# W123X.net
KiCad netlist of a schematic drawn in EAGLE
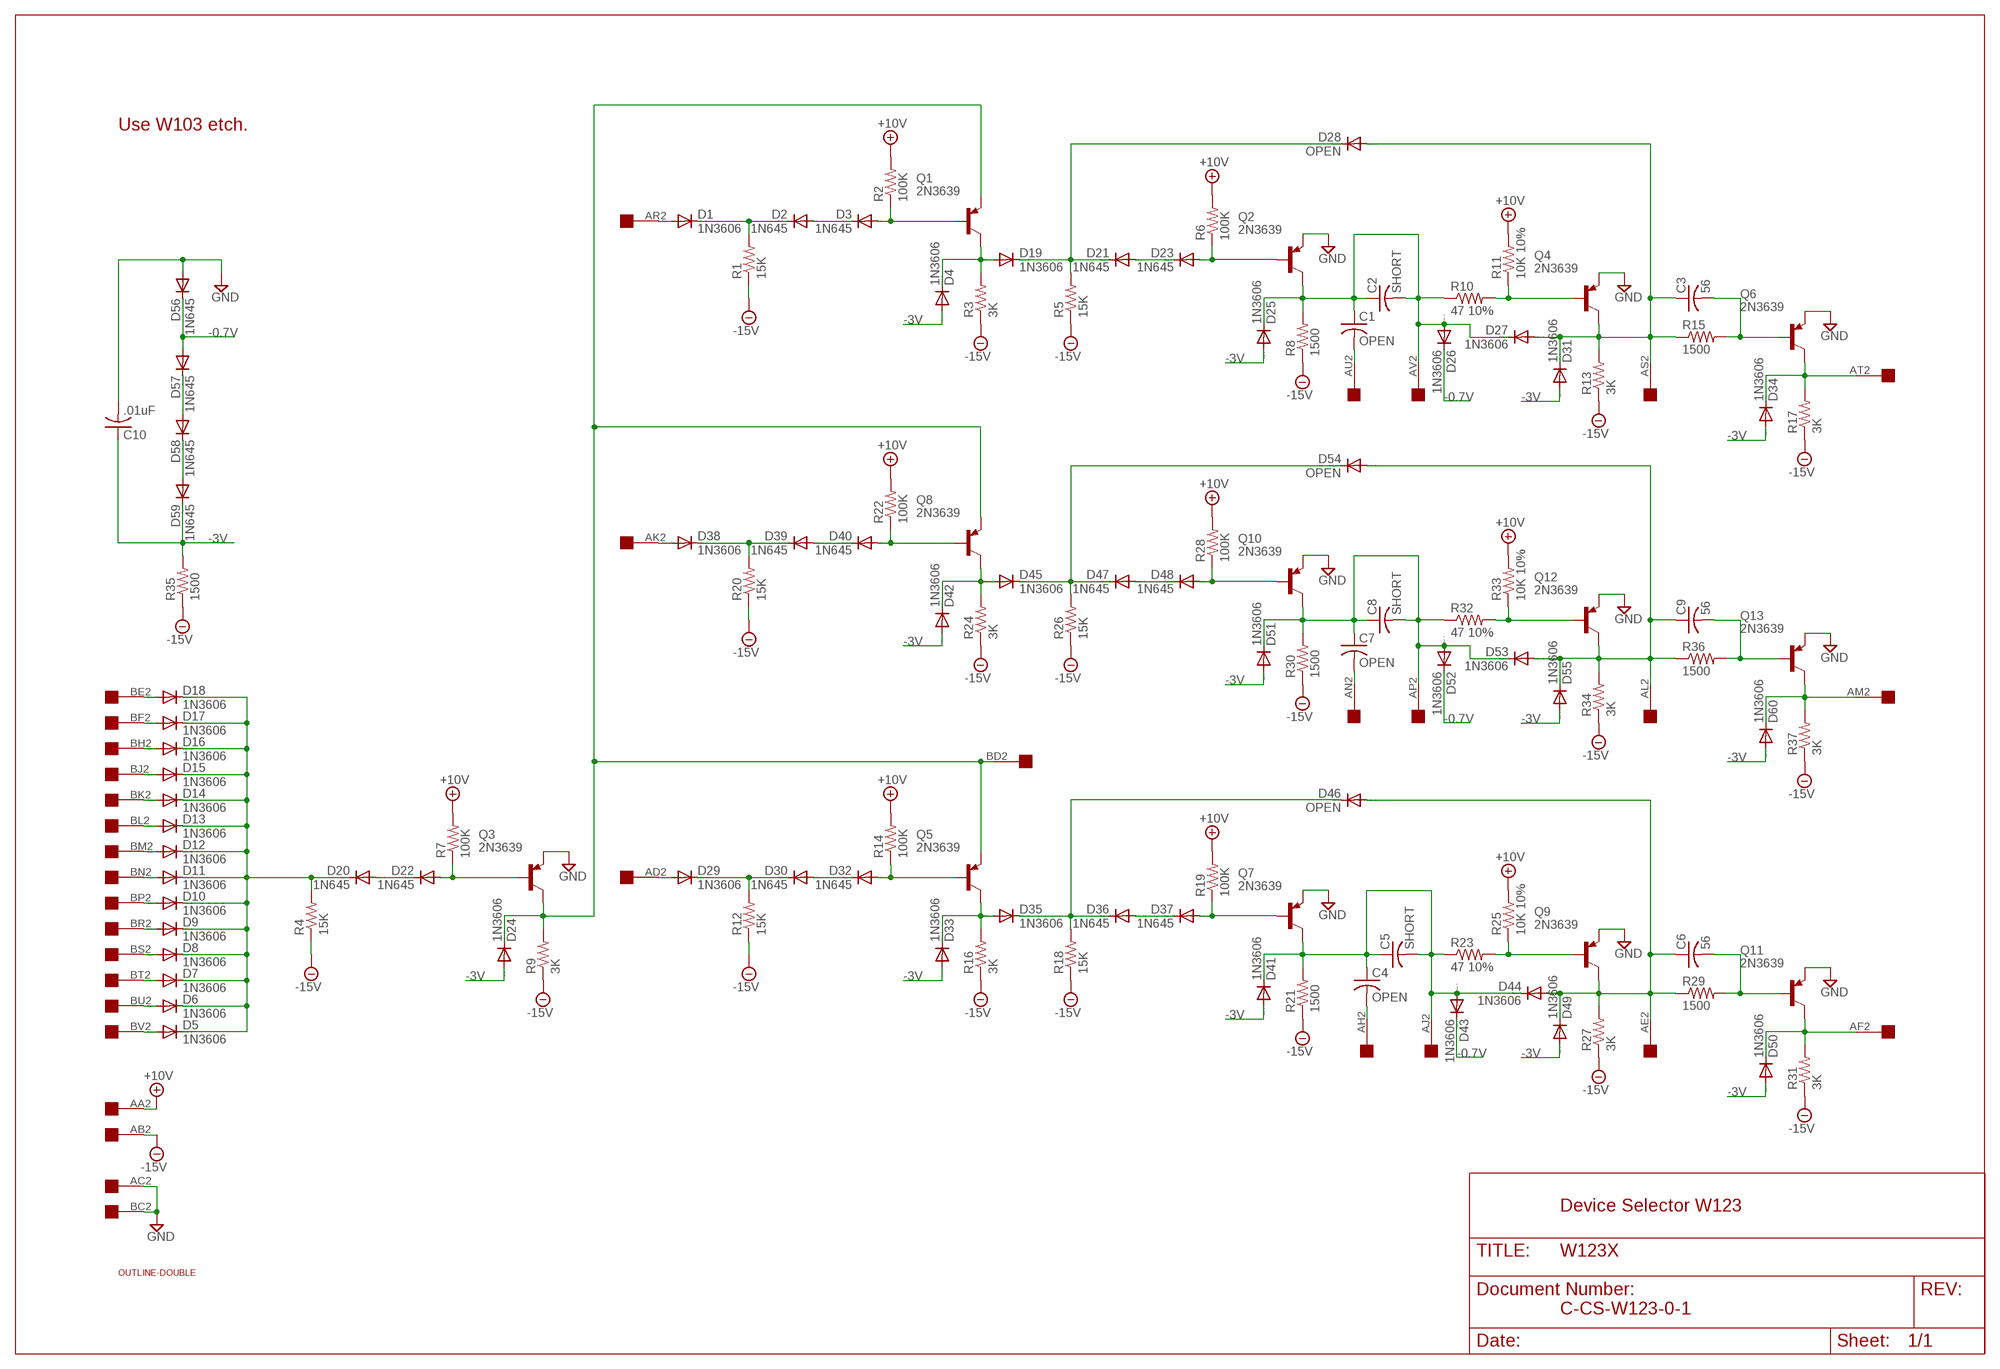
[diagram p0: schematic, sheet 1]

(export (version "E")
  (design (tool "Eeschema 10.0.6"))
  (components
    (comp (ref "C1")
      (value "OPEN")
      (footprint "eagle-import:C075-032X103")
      (libsource (lib "eagle-import") (part "C-US075-032X103"))
    )
    (comp (ref "C2")
      (value "SHORT")
      (footprint "eagle-import:C075-032X103")
      (libsource (lib "eagle-import") (part "C-US075-032X103"))
    )
    (comp (ref "C3")
      (value "56")
      (footprint "eagle-import:C075-032X103")
      (libsource (lib "eagle-import") (part "C-US075-032X103"))
    )
    (comp (ref "C4")
      (value "OPEN")
      (footprint "eagle-import:C075-032X103")
      (libsource (lib "eagle-import") (part "C-US075-032X103"))
    )
    (comp (ref "C5")
      (value "SHORT")
      (footprint "eagle-import:C075-032X103")
      (libsource (lib "eagle-import") (part "C-US075-032X103"))
    )
    (comp (ref "C6")
      (value "56")
      (footprint "eagle-import:C075-032X103")
      (libsource (lib "eagle-import") (part "C-US075-032X103"))
    )
    (comp (ref "C7")
      (value "OPEN")
      (footprint "eagle-import:C075-032X103")
      (libsource (lib "eagle-import") (part "C-US075-032X103"))
    )
    (comp (ref "C8")
      (value "SHORT")
      (footprint "eagle-import:C075-032X103")
      (libsource (lib "eagle-import") (part "C-US075-032X103"))
    )
    (comp (ref "C9")
      (value "56")
      (footprint "eagle-import:C075-032X103")
      (libsource (lib "eagle-import") (part "C-US075-032X103"))
    )
    (comp (ref "C10")
      (value ".01uF")
      (footprint "eagle-import:C075-032X103")
      (libsource (lib "eagle-import") (part "C-US075-032X103"))
    )
    (comp (ref "D1")
      (value "1N3606")
      (footprint "eagle-import:DO35-10")
      (libsource (lib "eagle-import") (part "1N4148DO35-10"))
    )
    (comp (ref "D2")
      (value "1N645")
      (footprint "eagle-import:DO35-10")
      (libsource (lib "eagle-import") (part "1N4148DO35-10"))
    )
    (comp (ref "D3")
      (value "1N645")
      (footprint "eagle-import:DO35-10")
      (libsource (lib "eagle-import") (part "1N4148DO35-10"))
    )
    (comp (ref "D4")
      (value "1N3606")
      (footprint "eagle-import:DO35-10")
      (libsource (lib "eagle-import") (part "1N4148DO35-10"))
    )
    (comp (ref "D5")
      (value "1N3606")
      (footprint "eagle-import:DO35-10")
      (libsource (lib "eagle-import") (part "1N4148DO35-10"))
    )
    (comp (ref "D6")
      (value "1N3606")
      (footprint "eagle-import:DO35-10")
      (libsource (lib "eagle-import") (part "1N4148DO35-10"))
    )
    (comp (ref "D7")
      (value "1N3606")
      (footprint "eagle-import:DO35-10")
      (libsource (lib "eagle-import") (part "1N4148DO35-10"))
    )
    (comp (ref "D8")
      (value "1N3606")
      (footprint "eagle-import:DO35-10")
      (libsource (lib "eagle-import") (part "1N4148DO35-10"))
    )
    (comp (ref "D9")
      (value "1N3606")
      (footprint "eagle-import:DO35-10")
      (libsource (lib "eagle-import") (part "1N4148DO35-10"))
    )
    (comp (ref "D10")
      (value "1N3606")
      (footprint "eagle-import:DO35-10")
      (libsource (lib "eagle-import") (part "1N4148DO35-10"))
    )
    (comp (ref "D11")
      (value "1N3606")
      (footprint "eagle-import:DO35-10")
      (libsource (lib "eagle-import") (part "1N4148DO35-10"))
    )
    (comp (ref "D12")
      (value "1N3606")
      (footprint "eagle-import:DO35-10")
      (libsource (lib "eagle-import") (part "1N4148DO35-10"))
    )
    (comp (ref "D13")
      (value "1N3606")
      (footprint "eagle-import:DO35-10")
      (libsource (lib "eagle-import") (part "1N4148DO35-10"))
    )
    (comp (ref "D14")
      (value "1N3606")
      (footprint "eagle-import:DO35-10")
      (libsource (lib "eagle-import") (part "1N4148DO35-10"))
    )
    (comp (ref "D15")
      (value "1N3606")
      (footprint "eagle-import:DO35-10")
      (libsource (lib "eagle-import") (part "1N4148DO35-10"))
    )
    (comp (ref "D16")
      (value "1N3606")
      (footprint "eagle-import:DO35-10")
      (libsource (lib "eagle-import") (part "1N4148DO35-10"))
    )
    (comp (ref "D17")
      (value "1N3606")
      (footprint "eagle-import:DO35-10")
      (libsource (lib "eagle-import") (part "1N4148DO35-10"))
    )
    (comp (ref "D18")
      (value "1N3606")
      (footprint "eagle-import:DO35-10")
      (libsource (lib "eagle-import") (part "1N4148DO35-10"))
    )
    (comp (ref "D19")
      (value "1N3606")
      (footprint "eagle-import:DO35-10")
      (libsource (lib "eagle-import") (part "1N4148DO35-10"))
    )
    (comp (ref "D20")
      (value "1N645")
      (footprint "eagle-import:DO35-10")
      (libsource (lib "eagle-import") (part "1N4148DO35-10"))
    )
    (comp (ref "D21")
      (value "1N645")
      (footprint "eagle-import:DO35-10")
      (libsource (lib "eagle-import") (part "1N4148DO35-10"))
    )
    (comp (ref "D22")
      (value "1N645")
      (footprint "eagle-import:DO35-10")
      (libsource (lib "eagle-import") (part "1N4148DO35-10"))
    )
    (comp (ref "D23")
      (value "1N645")
      (footprint "eagle-import:DO35-10")
      (libsource (lib "eagle-import") (part "1N4148DO35-10"))
    )
    (comp (ref "D24")
      (value "1N3606")
      (footprint "eagle-import:DO35-10")
      (libsource (lib "eagle-import") (part "1N4148DO35-10"))
    )
    (comp (ref "D25")
      (value "1N3606")
      (footprint "eagle-import:DO35-10")
      (libsource (lib "eagle-import") (part "1N4148DO35-10"))
    )
    (comp (ref "D26")
      (value "1N3606")
      (footprint "eagle-import:DO35-10")
      (libsource (lib "eagle-import") (part "1N4148DO35-10"))
    )
    (comp (ref "D27")
      (value "1N3606")
      (footprint "eagle-import:DO35-10")
      (libsource (lib "eagle-import") (part "1N4148DO35-10"))
    )
    (comp (ref "D28")
      (value "OPEN")
      (footprint "eagle-import:DO35-10")
      (libsource (lib "eagle-import") (part "1N4148DO35-10"))
    )
    (comp (ref "D29")
      (value "1N3606")
      (footprint "eagle-import:DO35-10")
      (libsource (lib "eagle-import") (part "1N4148DO35-10"))
    )
    (comp (ref "D30")
      (value "1N645")
      (footprint "eagle-import:DO35-10")
      (libsource (lib "eagle-import") (part "1N4148DO35-10"))
    )
    (comp (ref "D31")
      (value "1N3606")
      (footprint "eagle-import:DO35-10")
      (libsource (lib "eagle-import") (part "1N4148DO35-10"))
    )
    (comp (ref "D32")
      (value "1N645")
      (footprint "eagle-import:DO35-10")
      (libsource (lib "eagle-import") (part "1N4148DO35-10"))
    )
    (comp (ref "D33")
      (value "1N3606")
      (footprint "eagle-import:DO35-10")
      (libsource (lib "eagle-import") (part "1N4148DO35-10"))
    )
    (comp (ref "D34")
      (value "1N3606")
      (footprint "eagle-import:DO35-10")
      (libsource (lib "eagle-import") (part "1N4148DO35-10"))
    )
    (comp (ref "D35")
      (value "1N3606")
      (footprint "eagle-import:DO35-10")
      (libsource (lib "eagle-import") (part "1N4148DO35-10"))
    )
    (comp (ref "D36")
      (value "1N645")
      (footprint "eagle-import:DO35-10")
      (libsource (lib "eagle-import") (part "1N4148DO35-10"))
    )
    (comp (ref "D37")
      (value "1N645")
      (footprint "eagle-import:DO35-10")
      (libsource (lib "eagle-import") (part "1N4148DO35-10"))
    )
    (comp (ref "D38")
      (value "1N3606")
      (footprint "eagle-import:DO35-10")
      (libsource (lib "eagle-import") (part "1N4148DO35-10"))
    )
    (comp (ref "D39")
      (value "1N645")
      (footprint "eagle-import:DO35-10")
      (libsource (lib "eagle-import") (part "1N4148DO35-10"))
    )
    (comp (ref "D40")
      (value "1N645")
      (footprint "eagle-import:DO35-10")
      (libsource (lib "eagle-import") (part "1N4148DO35-10"))
    )
    (comp (ref "D41")
      (value "1N3606")
      (footprint "eagle-import:DO35-10")
      (libsource (lib "eagle-import") (part "1N4148DO35-10"))
    )
    (comp (ref "D42")
      (value "1N3606")
      (footprint "eagle-import:DO35-10")
      (libsource (lib "eagle-import") (part "1N4148DO35-10"))
    )
    (comp (ref "D43")
      (value "1N3606")
      (footprint "eagle-import:DO35-10")
      (libsource (lib "eagle-import") (part "1N4148DO35-10"))
    )
    (comp (ref "D44")
      (value "1N3606")
      (footprint "eagle-import:DO35-10")
      (libsource (lib "eagle-import") (part "1N4148DO35-10"))
    )
    (comp (ref "D45")
      (value "1N3606")
      (footprint "eagle-import:DO35-10")
      (libsource (lib "eagle-import") (part "1N4148DO35-10"))
    )
    (comp (ref "D46")
      (value "OPEN")
      (footprint "eagle-import:DO35-10")
      (libsource (lib "eagle-import") (part "1N4148DO35-10"))
    )
    (comp (ref "D47")
      (value "1N645")
      (footprint "eagle-import:DO35-10")
      (libsource (lib "eagle-import") (part "1N4148DO35-10"))
    )
    (comp (ref "D48")
      (value "1N645")
      (footprint "eagle-import:DO35-10")
      (libsource (lib "eagle-import") (part "1N4148DO35-10"))
    )
    (comp (ref "D49")
      (value "1N3606")
      (footprint "eagle-import:DO35-10")
      (libsource (lib "eagle-import") (part "1N4148DO35-10"))
    )
    (comp (ref "D50")
      (value "1N3606")
      (footprint "eagle-import:DO35-10")
      (libsource (lib "eagle-import") (part "1N4148DO35-10"))
    )
    (comp (ref "D51")
      (value "1N3606")
      (footprint "eagle-import:DO35-10")
      (libsource (lib "eagle-import") (part "1N4148DO35-10"))
    )
    (comp (ref "D52")
      (value "1N3606")
      (footprint "eagle-import:DO35-10")
      (libsource (lib "eagle-import") (part "1N4148DO35-10"))
    )
    (comp (ref "D53")
      (value "1N3606")
      (footprint "eagle-import:DO35-10")
      (libsource (lib "eagle-import") (part "1N4148DO35-10"))
    )
    (comp (ref "D54")
      (value "OPEN")
      (footprint "eagle-import:DO35-10")
      (libsource (lib "eagle-import") (part "1N4148DO35-10"))
    )
    (comp (ref "D55")
      (value "1N3606")
      (footprint "eagle-import:DO35-10")
      (libsource (lib "eagle-import") (part "1N4148DO35-10"))
    )
    (comp (ref "D56")
      (value "1N645")
      (footprint "eagle-import:DO35-10")
      (libsource (lib "eagle-import") (part "1N4148DO35-10"))
    )
    (comp (ref "D57")
      (value "1N645")
      (footprint "eagle-import:DO35-10")
      (libsource (lib "eagle-import") (part "1N4148DO35-10"))
    )
    (comp (ref "D58")
      (value "1N645")
      (footprint "eagle-import:DO35-10")
      (libsource (lib "eagle-import") (part "1N4148DO35-10"))
    )
    (comp (ref "D59")
      (value "1N645")
      (footprint "eagle-import:DO35-10")
      (libsource (lib "eagle-import") (part "1N4148DO35-10"))
    )
    (comp (ref "D60")
      (value "1N3606")
      (footprint "eagle-import:DO35-10")
      (libsource (lib "eagle-import") (part "1N4148DO35-10"))
    )
    (comp (ref "Q1")
      (value "2N3639")
      (footprint "eagle-import:TO39")
      (libsource (lib "eagle-import") (part "2N2904"))
    )
    (comp (ref "Q2")
      (value "2N3639")
      (footprint "eagle-import:TO39")
      (libsource (lib "eagle-import") (part "2N2904"))
    )
    (comp (ref "Q3")
      (value "2N3639")
      (footprint "eagle-import:TO39")
      (libsource (lib "eagle-import") (part "2N2904"))
    )
    (comp (ref "Q4")
      (value "2N3639")
      (footprint "eagle-import:TO39")
      (libsource (lib "eagle-import") (part "2N2904"))
    )
    (comp (ref "Q5")
      (value "2N3639")
      (footprint "eagle-import:TO39")
      (libsource (lib "eagle-import") (part "2N2904"))
    )
    (comp (ref "Q6")
      (value "2N3639")
      (footprint "eagle-import:TO39")
      (libsource (lib "eagle-import") (part "2N2904"))
    )
    (comp (ref "Q7")
      (value "2N3639")
      (footprint "eagle-import:TO39")
      (libsource (lib "eagle-import") (part "2N2904"))
    )
    (comp (ref "Q8")
      (value "2N3639")
      (footprint "eagle-import:TO39")
      (libsource (lib "eagle-import") (part "2N2904"))
    )
    (comp (ref "Q9")
      (value "2N3639")
      (footprint "eagle-import:TO39")
      (libsource (lib "eagle-import") (part "2N2904"))
    )
    (comp (ref "Q10")
      (value "2N3639")
      (footprint "eagle-import:TO39")
      (libsource (lib "eagle-import") (part "2N2904"))
    )
    (comp (ref "Q11")
      (value "2N3639")
      (footprint "eagle-import:TO39")
      (libsource (lib "eagle-import") (part "2N2904"))
    )
    (comp (ref "Q12")
      (value "2N3639")
      (footprint "eagle-import:TO39")
      (libsource (lib "eagle-import") (part "2N2904"))
    )
    (comp (ref "Q13")
      (value "2N3639")
      (footprint "eagle-import:TO39")
      (libsource (lib "eagle-import") (part "2N2904"))
    )
    (comp (ref "R1")
      (value "15K")
      (footprint "eagle-import:0207_10")
      (libsource (lib "eagle-import") (part "R-US_0207/10"))
    )
    (comp (ref "R2")
      (value "100K")
      (footprint "eagle-import:0207_10")
      (libsource (lib "eagle-import") (part "R-US_0207/10"))
    )
    (comp (ref "R3")
      (value "3K")
      (footprint "eagle-import:0207_10")
      (libsource (lib "eagle-import") (part "R-US_0207/10"))
    )
    (comp (ref "R4")
      (value "15K")
      (footprint "eagle-import:0207_10")
      (libsource (lib "eagle-import") (part "R-US_0207/10"))
    )
    (comp (ref "R5")
      (value "15K")
      (footprint "eagle-import:0207_10")
      (libsource (lib "eagle-import") (part "R-US_0207/10"))
    )
    (comp (ref "R6")
      (value "100K")
      (footprint "eagle-import:0207_10")
      (libsource (lib "eagle-import") (part "R-US_0207/10"))
    )
    (comp (ref "R7")
      (value "100K")
      (footprint "eagle-import:0207_10")
      (libsource (lib "eagle-import") (part "R-US_0207/10"))
    )
    (comp (ref "R8")
      (value "1500")
      (footprint "eagle-import:0207_10")
      (libsource (lib "eagle-import") (part "R-US_0207/10"))
    )
    (comp (ref "R9")
      (value "3K")
      (footprint "eagle-import:0207_10")
      (libsource (lib "eagle-import") (part "R-US_0207/10"))
    )
    (comp (ref "R10")
      (value "47 10%")
      (footprint "eagle-import:0207_10")
      (libsource (lib "eagle-import") (part "R-US_0207/10"))
    )
    (comp (ref "R11")
      (value "10K 10%")
      (footprint "eagle-import:0207_10")
      (libsource (lib "eagle-import") (part "R-US_0207/10"))
    )
    (comp (ref "R12")
      (value "15K")
      (footprint "eagle-import:0207_10")
      (libsource (lib "eagle-import") (part "R-US_0207/10"))
    )
    (comp (ref "R13")
      (value "3K")
      (footprint "eagle-import:0207_10")
      (libsource (lib "eagle-import") (part "R-US_0207/10"))
    )
    (comp (ref "R14")
      (value "100K")
      (footprint "eagle-import:0207_10")
      (libsource (lib "eagle-import") (part "R-US_0207/10"))
    )
    (comp (ref "R15")
      (value "1500")
      (footprint "eagle-import:0207_10")
      (libsource (lib "eagle-import") (part "R-US_0207/10"))
    )
    (comp (ref "R16")
      (value "3K")
      (footprint "eagle-import:0207_10")
      (libsource (lib "eagle-import") (part "R-US_0207/10"))
    )
    (comp (ref "R17")
      (value "3K")
      (footprint "eagle-import:0207_10")
      (libsource (lib "eagle-import") (part "R-US_0207/10"))
    )
    (comp (ref "R18")
      (value "15K")
      (footprint "eagle-import:0207_10")
      (libsource (lib "eagle-import") (part "R-US_0207/10"))
    )
    (comp (ref "R19")
      (value "100K")
      (footprint "eagle-import:0207_10")
      (libsource (lib "eagle-import") (part "R-US_0207/10"))
    )
    (comp (ref "R20")
      (value "15K")
      (footprint "eagle-import:0207_10")
      (libsource (lib "eagle-import") (part "R-US_0207/10"))
    )
    (comp (ref "R21")
      (value "1500")
      (footprint "eagle-import:0207_10")
      (libsource (lib "eagle-import") (part "R-US_0207/10"))
    )
    (comp (ref "R22")
      (value "100K")
      (footprint "eagle-import:0207_10")
      (libsource (lib "eagle-import") (part "R-US_0207/10"))
    )
    (comp (ref "R23")
      (value "47 10%")
      (footprint "eagle-import:0207_10")
      (libsource (lib "eagle-import") (part "R-US_0207/10"))
    )
    (comp (ref "R24")
      (value "3K")
      (footprint "eagle-import:0207_10")
      (libsource (lib "eagle-import") (part "R-US_0207/10"))
    )
    (comp (ref "R25")
      (value "10K 10%")
      (footprint "eagle-import:0207_10")
      (libsource (lib "eagle-import") (part "R-US_0207/10"))
    )
    (comp (ref "R26")
      (value "15K")
      (footprint "eagle-import:0207_10")
      (libsource (lib "eagle-import") (part "R-US_0207/10"))
    )
    (comp (ref "R27")
      (value "3K")
      (footprint "eagle-import:0207_10")
      (libsource (lib "eagle-import") (part "R-US_0207/10"))
    )
    (comp (ref "R28")
      (value "100K")
      (footprint "eagle-import:0207_10")
      (libsource (lib "eagle-import") (part "R-US_0207/10"))
    )
    (comp (ref "R29")
      (value "1500")
      (footprint "eagle-import:0207_10")
      (libsource (lib "eagle-import") (part "R-US_0207/10"))
    )
    (comp (ref "R30")
      (value "1500")
      (footprint "eagle-import:0207_10")
      (libsource (lib "eagle-import") (part "R-US_0207/10"))
    )
    (comp (ref "R31")
      (value "3K")
      (footprint "eagle-import:0207_10")
      (libsource (lib "eagle-import") (part "R-US_0207/10"))
    )
    (comp (ref "R32")
      (value "47 10%")
      (footprint "eagle-import:0207_10")
      (libsource (lib "eagle-import") (part "R-US_0207/10"))
    )
    (comp (ref "R33")
      (value "10K 10%")
      (footprint "eagle-import:0207_10")
      (libsource (lib "eagle-import") (part "R-US_0207/10"))
    )
    (comp (ref "R34")
      (value "3K")
      (footprint "eagle-import:0207_10")
      (libsource (lib "eagle-import") (part "R-US_0207/10"))
    )
    (comp (ref "R35")
      (value "1500")
      (footprint "eagle-import:0207_10")
      (libsource (lib "eagle-import") (part "R-US_0207/10"))
    )
    (comp (ref "R36")
      (value "1500")
      (footprint "eagle-import:0207_10")
      (libsource (lib "eagle-import") (part "R-US_0207/10"))
    )
    (comp (ref "R37")
      (value "3K")
      (footprint "eagle-import:0207_10")
      (libsource (lib "eagle-import") (part "R-US_0207/10"))
    )
    (comp (ref "U$1")
      (value "OUTLINE-DOUBLE")
      (footprint "eagle-import:DOUBLE")
      (libsource (lib "eagle-import") (part "OUTLINE-DOUBLE"))
    )
    (comp (ref "U$2")
      (value "DOUBLE")
      (footprint "eagle-import:EDGE-CON4")
      (libsource (lib "eagle-import") (part "DOUBLE"))
    )
  )
  (nets
    (net (code "1") (name "+10V") (class "Default")
      (node (ref "R11") (pin "2") (pinfunction "2_2") (pintype "passive"))
      (node (ref "R14") (pin "2") (pinfunction "2_2") (pintype "passive"))
      (node (ref "R19") (pin "2") (pinfunction "2_2") (pintype "passive"))
      (node (ref "R2") (pin "2") (pinfunction "2_2") (pintype "passive"))
      (node (ref "R22") (pin "2") (pinfunction "2_2") (pintype "passive"))
      (node (ref "R25") (pin "2") (pinfunction "2_2") (pintype "passive"))
      (node (ref "R28") (pin "2") (pinfunction "2_2") (pintype "passive"))
      (node (ref "R33") (pin "2") (pinfunction "2_2") (pintype "passive"))
      (node (ref "R6") (pin "2") (pinfunction "2_2") (pintype "passive"))
      (node (ref "R7") (pin "2") (pinfunction "2_2") (pintype "passive"))
      (node (ref "U$2") (pin "AA2") (pinfunction "1_AA2") (pintype "bidirectional"))
    )
    (net (code "2") (name "-15V") (class "Default")
      (node (ref "R1") (pin "1") (pinfunction "1_1") (pintype "passive"))
      (node (ref "R12") (pin "1") (pinfunction "1_1") (pintype "passive"))
      (node (ref "R13") (pin "1") (pinfunction "1_1") (pintype "passive"))
      (node (ref "R16") (pin "1") (pinfunction "1_1") (pintype "passive"))
      (node (ref "R17") (pin "1") (pinfunction "1_1") (pintype "passive"))
      (node (ref "R18") (pin "1") (pinfunction "1_1") (pintype "passive"))
      (node (ref "R20") (pin "1") (pinfunction "1_1") (pintype "passive"))
      (node (ref "R21") (pin "1") (pinfunction "1_1") (pintype "passive"))
      (node (ref "R24") (pin "1") (pinfunction "1_1") (pintype "passive"))
      (node (ref "R26") (pin "1") (pinfunction "1_1") (pintype "passive"))
      (node (ref "R27") (pin "1") (pinfunction "1_1") (pintype "passive"))
      (node (ref "R3") (pin "1") (pinfunction "1_1") (pintype "passive"))
      (node (ref "R30") (pin "1") (pinfunction "1_1") (pintype "passive"))
      (node (ref "R31") (pin "1") (pinfunction "1_1") (pintype "passive"))
      (node (ref "R34") (pin "1") (pinfunction "1_1") (pintype "passive"))
      (node (ref "R35") (pin "1") (pinfunction "1_1") (pintype "passive"))
      (node (ref "R37") (pin "1") (pinfunction "1_1") (pintype "passive"))
      (node (ref "R4") (pin "1") (pinfunction "1_1") (pintype "passive"))
      (node (ref "R5") (pin "1") (pinfunction "1_1") (pintype "passive"))
      (node (ref "R8") (pin "1") (pinfunction "1_1") (pintype "passive"))
      (node (ref "R9") (pin "1") (pinfunction "1_1") (pintype "passive"))
      (node (ref "U$2") (pin "AB2") (pinfunction "1_AB2") (pintype "bidirectional"))
    )
    (net (code "3") (name "/-0.7V") (class "Default")
      (node (ref "D26") (pin "C") (pinfunction "C_C") (pintype "passive"))
      (node (ref "D43") (pin "C") (pinfunction "C_C") (pintype "passive"))
      (node (ref "D52") (pin "C") (pinfunction "C_C") (pintype "passive"))
      (node (ref "D56") (pin "C") (pinfunction "C_C") (pintype "passive"))
      (node (ref "D57") (pin "A") (pinfunction "A_A") (pintype "passive"))
    )
    (net (code "4") (name "/-3V") (class "Default")
      (node (ref "C10") (pin "1") (pinfunction "1_1") (pintype "passive"))
      (node (ref "D24") (pin "A") (pinfunction "A_A") (pintype "passive"))
      (node (ref "D25") (pin "A") (pinfunction "A_A") (pintype "passive"))
      (node (ref "D31") (pin "A") (pinfunction "A_A") (pintype "passive"))
      (node (ref "D33") (pin "A") (pinfunction "A_A") (pintype "passive"))
      (node (ref "D34") (pin "A") (pinfunction "A_A") (pintype "passive"))
      (node (ref "D4") (pin "A") (pinfunction "A_A") (pintype "passive"))
      (node (ref "D41") (pin "A") (pinfunction "A_A") (pintype "passive"))
      (node (ref "D42") (pin "A") (pinfunction "A_A") (pintype "passive"))
      (node (ref "D49") (pin "A") (pinfunction "A_A") (pintype "passive"))
      (node (ref "D50") (pin "A") (pinfunction "A_A") (pintype "passive"))
      (node (ref "D51") (pin "A") (pinfunction "A_A") (pintype "passive"))
      (node (ref "D55") (pin "A") (pinfunction "A_A") (pintype "passive"))
      (node (ref "D59") (pin "C") (pinfunction "C_C") (pintype "passive"))
      (node (ref "D60") (pin "A") (pinfunction "A_A") (pintype "passive"))
      (node (ref "R35") (pin "2") (pinfunction "2_2") (pintype "passive"))
    )
    (net (code "5") (name "GND") (class "Default")
      (node (ref "C10") (pin "2") (pinfunction "2_2") (pintype "passive"))
      (node (ref "D56") (pin "A") (pinfunction "A_A") (pintype "passive"))
      (node (ref "Q10") (pin "1") (pinfunction "E_1") (pintype "passive"))
      (node (ref "Q11") (pin "1") (pinfunction "E_1") (pintype "passive"))
      (node (ref "Q12") (pin "1") (pinfunction "E_1") (pintype "passive"))
      (node (ref "Q13") (pin "1") (pinfunction "E_1") (pintype "passive"))
      (node (ref "Q2") (pin "1") (pinfunction "E_1") (pintype "passive"))
      (node (ref "Q3") (pin "1") (pinfunction "E_1") (pintype "passive"))
      (node (ref "Q4") (pin "1") (pinfunction "E_1") (pintype "passive"))
      (node (ref "Q6") (pin "1") (pinfunction "E_1") (pintype "passive"))
      (node (ref "Q7") (pin "1") (pinfunction "E_1") (pintype "passive"))
      (node (ref "Q9") (pin "1") (pinfunction "E_1") (pintype "passive"))
      (node (ref "U$2") (pin "AC2") (pinfunction "1_AC2") (pintype "bidirectional"))
      (node (ref "U$2") (pin "BC2") (pinfunction "1_BC2") (pintype "bidirectional"))
    )
    (net (code "6") (name "Net-(D1-PadC)") (class "Default")
      (node (ref "D1") (pin "C") (pinfunction "C_C") (pintype "passive"))
      (node (ref "D2") (pin "C") (pinfunction "C_C") (pintype "passive"))
      (node (ref "R1") (pin "2") (pinfunction "2_2") (pintype "passive"))
    )
    (net (code "7") (name "Net-(D2-PadA)") (class "Default")
      (node (ref "D2") (pin "A") (pinfunction "A_A") (pintype "passive"))
      (node (ref "D3") (pin "C") (pinfunction "C_C") (pintype "passive"))
    )
    (net (code "8") (name "Net-(D10-PadC)") (class "Default")
      (node (ref "D10") (pin "C") (pinfunction "C_C") (pintype "passive"))
      (node (ref "D11") (pin "C") (pinfunction "C_C") (pintype "passive"))
      (node (ref "D12") (pin "C") (pinfunction "C_C") (pintype "passive"))
      (node (ref "D13") (pin "C") (pinfunction "C_C") (pintype "passive"))
      (node (ref "D14") (pin "C") (pinfunction "C_C") (pintype "passive"))
      (node (ref "D15") (pin "C") (pinfunction "C_C") (pintype "passive"))
      (node (ref "D16") (pin "C") (pinfunction "C_C") (pintype "passive"))
      (node (ref "D17") (pin "C") (pinfunction "C_C") (pintype "passive"))
      (node (ref "D18") (pin "C") (pinfunction "C_C") (pintype "passive"))
      (node (ref "D20") (pin "C") (pinfunction "C_C") (pintype "passive"))
      (node (ref "D5") (pin "C") (pinfunction "C_C") (pintype "passive"))
      (node (ref "D6") (pin "C") (pinfunction "C_C") (pintype "passive"))
      (node (ref "D7") (pin "C") (pinfunction "C_C") (pintype "passive"))
      (node (ref "D8") (pin "C") (pinfunction "C_C") (pintype "passive"))
      (node (ref "D9") (pin "C") (pinfunction "C_C") (pintype "passive"))
      (node (ref "R4") (pin "2") (pinfunction "2_2") (pintype "passive"))
    )
    (net (code "9") (name "Net-(D19-PadC)") (class "Default")
      (node (ref "D19") (pin "C") (pinfunction "C_C") (pintype "passive"))
      (node (ref "D21") (pin "C") (pinfunction "C_C") (pintype "passive"))
      (node (ref "D28") (pin "C") (pinfunction "C_C") (pintype "passive"))
      (node (ref "R5") (pin "2") (pinfunction "2_2") (pintype "passive"))
    )
    (net (code "10") (name "Net-(D20-PadA)") (class "Default")
      (node (ref "D20") (pin "A") (pinfunction "A_A") (pintype "passive"))
      (node (ref "D22") (pin "C") (pinfunction "C_C") (pintype "passive"))
    )
    (net (code "11") (name "Net-(D21-PadA)") (class "Default")
      (node (ref "D21") (pin "A") (pinfunction "A_A") (pintype "passive"))
      (node (ref "D23") (pin "C") (pinfunction "C_C") (pintype "passive"))
    )
    (net (code "12") (name "Net-(D29-PadC)") (class "Default")
      (node (ref "D29") (pin "C") (pinfunction "C_C") (pintype "passive"))
      (node (ref "D30") (pin "C") (pinfunction "C_C") (pintype "passive"))
      (node (ref "R12") (pin "2") (pinfunction "2_2") (pintype "passive"))
    )
    (net (code "13") (name "Net-(D30-PadA)") (class "Default")
      (node (ref "D30") (pin "A") (pinfunction "A_A") (pintype "passive"))
      (node (ref "D32") (pin "C") (pinfunction "C_C") (pintype "passive"))
    )
    (net (code "14") (name "Net-(D35-PadC)") (class "Default")
      (node (ref "D35") (pin "C") (pinfunction "C_C") (pintype "passive"))
      (node (ref "D36") (pin "C") (pinfunction "C_C") (pintype "passive"))
      (node (ref "D46") (pin "C") (pinfunction "C_C") (pintype "passive"))
      (node (ref "R18") (pin "2") (pinfunction "2_2") (pintype "passive"))
    )
    (net (code "15") (name "Net-(D36-PadA)") (class "Default")
      (node (ref "D36") (pin "A") (pinfunction "A_A") (pintype "passive"))
      (node (ref "D37") (pin "C") (pinfunction "C_C") (pintype "passive"))
    )
    (net (code "16") (name "Net-(D38-PadC)") (class "Default")
      (node (ref "D38") (pin "C") (pinfunction "C_C") (pintype "passive"))
      (node (ref "D39") (pin "C") (pinfunction "C_C") (pintype "passive"))
      (node (ref "R20") (pin "2") (pinfunction "2_2") (pintype "passive"))
    )
    (net (code "17") (name "Net-(D39-PadA)") (class "Default")
      (node (ref "D39") (pin "A") (pinfunction "A_A") (pintype "passive"))
      (node (ref "D40") (pin "C") (pinfunction "C_C") (pintype "passive"))
    )
    (net (code "18") (name "Net-(D45-PadC)") (class "Default")
      (node (ref "D45") (pin "C") (pinfunction "C_C") (pintype "passive"))
      (node (ref "D47") (pin "C") (pinfunction "C_C") (pintype "passive"))
      (node (ref "D54") (pin "C") (pinfunction "C_C") (pintype "passive"))
      (node (ref "R26") (pin "2") (pinfunction "2_2") (pintype "passive"))
    )
    (net (code "19") (name "Net-(D47-PadA)") (class "Default")
      (node (ref "D47") (pin "A") (pinfunction "A_A") (pintype "passive"))
      (node (ref "D48") (pin "C") (pinfunction "C_C") (pintype "passive"))
    )
    (net (code "20") (name "Net-(D57-PadC)") (class "Default")
      (node (ref "D57") (pin "C") (pinfunction "C_C") (pintype "passive"))
      (node (ref "D58") (pin "A") (pinfunction "A_A") (pintype "passive"))
    )
    (net (code "21") (name "Net-(D58-PadC)") (class "Default")
      (node (ref "D58") (pin "C") (pinfunction "C_C") (pintype "passive"))
      (node (ref "D59") (pin "A") (pinfunction "A_A") (pintype "passive"))
    )
    (net (code "22") (name "Net-(Q1-B)") (class "Default")
      (node (ref "D3") (pin "A") (pinfunction "A_A") (pintype "passive"))
      (node (ref "Q1") (pin "2") (pinfunction "B_2") (pintype "passive"))
      (node (ref "R2") (pin "1") (pinfunction "1_1") (pintype "passive"))
    )
    (net (code "23") (name "Net-(Q1-C)") (class "Default")
      (node (ref "D19") (pin "A") (pinfunction "A_A") (pintype "passive"))
      (node (ref "D4") (pin "C") (pinfunction "C_C") (pintype "passive"))
      (node (ref "Q1") (pin "3") (pinfunction "C_3") (pintype "passive"))
      (node (ref "R3") (pin "2") (pinfunction "2_2") (pintype "passive"))
    )
    (net (code "24") (name "Net-(Q1-E)") (class "Default")
      (node (ref "D24") (pin "C") (pinfunction "C_C") (pintype "passive"))
      (node (ref "Q1") (pin "1") (pinfunction "E_1") (pintype "passive"))
      (node (ref "Q3") (pin "3") (pinfunction "C_3") (pintype "passive"))
      (node (ref "Q5") (pin "1") (pinfunction "E_1") (pintype "passive"))
      (node (ref "Q8") (pin "1") (pinfunction "E_1") (pintype "passive"))
      (node (ref "R9") (pin "2") (pinfunction "2_2") (pintype "passive"))
      (node (ref "U$2") (pin "BD2") (pinfunction "1_BD2") (pintype "bidirectional"))
    )
    (net (code "25") (name "Net-(Q2-B)") (class "Default")
      (node (ref "D23") (pin "A") (pinfunction "A_A") (pintype "passive"))
      (node (ref "Q2") (pin "2") (pinfunction "B_2") (pintype "passive"))
      (node (ref "R6") (pin "1") (pinfunction "1_1") (pintype "passive"))
    )
    (net (code "26") (name "Net-(Q2-C)") (class "Default")
      (node (ref "C1") (pin "1") (pinfunction "1_1") (pintype "passive"))
      (node (ref "C2") (pin "1") (pinfunction "1_1") (pintype "passive"))
      (node (ref "C2") (pin "2") (pinfunction "2_2") (pintype "passive"))
      (node (ref "D25") (pin "C") (pinfunction "C_C") (pintype "passive"))
      (node (ref "D26") (pin "A") (pinfunction "A_A") (pintype "passive"))
      (node (ref "D27") (pin "C") (pinfunction "C_C") (pintype "passive"))
      (node (ref "Q2") (pin "3") (pinfunction "C_3") (pintype "passive"))
      (node (ref "R10") (pin "1") (pinfunction "1_1") (pintype "passive"))
      (node (ref "R8") (pin "2") (pinfunction "2_2") (pintype "passive"))
      (node (ref "U$2") (pin "AV2") (pinfunction "1_AV2") (pintype "bidirectional"))
    )
    (net (code "27") (name "Net-(Q3-B)") (class "Default")
      (node (ref "D22") (pin "A") (pinfunction "A_A") (pintype "passive"))
      (node (ref "Q3") (pin "2") (pinfunction "B_2") (pintype "passive"))
      (node (ref "R7") (pin "1") (pinfunction "1_1") (pintype "passive"))
    )
    (net (code "28") (name "Net-(Q4-B)") (class "Default")
      (node (ref "Q4") (pin "2") (pinfunction "B_2") (pintype "passive"))
      (node (ref "R10") (pin "2") (pinfunction "2_2") (pintype "passive"))
      (node (ref "R11") (pin "1") (pinfunction "1_1") (pintype "passive"))
    )
    (net (code "29") (name "Net-(Q4-C)") (class "Default")
      (node (ref "C3") (pin "1") (pinfunction "1_1") (pintype "passive"))
      (node (ref "D27") (pin "A") (pinfunction "A_A") (pintype "passive"))
      (node (ref "D28") (pin "A") (pinfunction "A_A") (pintype "passive"))
      (node (ref "D31") (pin "C") (pinfunction "C_C") (pintype "passive"))
      (node (ref "Q4") (pin "3") (pinfunction "C_3") (pintype "passive"))
      (node (ref "R13") (pin "2") (pinfunction "2_2") (pintype "passive"))
      (node (ref "R15") (pin "1") (pinfunction "1_1") (pintype "passive"))
      (node (ref "U$2") (pin "AS2") (pinfunction "1_AS2") (pintype "bidirectional"))
    )
    (net (code "30") (name "Net-(Q5-B)") (class "Default")
      (node (ref "D32") (pin "A") (pinfunction "A_A") (pintype "passive"))
      (node (ref "Q5") (pin "2") (pinfunction "B_2") (pintype "passive"))
      (node (ref "R14") (pin "1") (pinfunction "1_1") (pintype "passive"))
    )
    (net (code "31") (name "Net-(Q5-C)") (class "Default")
      (node (ref "D33") (pin "C") (pinfunction "C_C") (pintype "passive"))
      (node (ref "D35") (pin "A") (pinfunction "A_A") (pintype "passive"))
      (node (ref "Q5") (pin "3") (pinfunction "C_3") (pintype "passive"))
      (node (ref "R16") (pin "2") (pinfunction "2_2") (pintype "passive"))
    )
    (net (code "32") (name "Net-(Q6-B)") (class "Default")
      (node (ref "C3") (pin "2") (pinfunction "2_2") (pintype "passive"))
      (node (ref "Q6") (pin "2") (pinfunction "B_2") (pintype "passive"))
      (node (ref "R15") (pin "2") (pinfunction "2_2") (pintype "passive"))
    )
    (net (code "33") (name "Net-(Q6-C)") (class "Default")
      (node (ref "D34") (pin "C") (pinfunction "C_C") (pintype "passive"))
      (node (ref "Q6") (pin "3") (pinfunction "C_3") (pintype "passive"))
      (node (ref "R17") (pin "2") (pinfunction "2_2") (pintype "passive"))
      (node (ref "U$2") (pin "AT2") (pinfunction "1_AT2") (pintype "bidirectional"))
    )
    (net (code "34") (name "Net-(Q7-B)") (class "Default")
      (node (ref "D37") (pin "A") (pinfunction "A_A") (pintype "passive"))
      (node (ref "Q7") (pin "2") (pinfunction "B_2") (pintype "passive"))
      (node (ref "R19") (pin "1") (pinfunction "1_1") (pintype "passive"))
    )
    (net (code "35") (name "Net-(Q7-C)") (class "Default")
      (node (ref "C4") (pin "1") (pinfunction "1_1") (pintype "passive"))
      (node (ref "C5") (pin "1") (pinfunction "1_1") (pintype "passive"))
      (node (ref "C5") (pin "2") (pinfunction "2_2") (pintype "passive"))
      (node (ref "D41") (pin "C") (pinfunction "C_C") (pintype "passive"))
      (node (ref "D43") (pin "A") (pinfunction "A_A") (pintype "passive"))
      (node (ref "D44") (pin "C") (pinfunction "C_C") (pintype "passive"))
      (node (ref "Q7") (pin "3") (pinfunction "C_3") (pintype "passive"))
      (node (ref "R21") (pin "2") (pinfunction "2_2") (pintype "passive"))
      (node (ref "R23") (pin "1") (pinfunction "1_1") (pintype "passive"))
      (node (ref "U$2") (pin "AJ2") (pinfunction "1_AJ2") (pintype "bidirectional"))
    )
    (net (code "36") (name "Net-(Q8-B)") (class "Default")
      (node (ref "D40") (pin "A") (pinfunction "A_A") (pintype "passive"))
      (node (ref "Q8") (pin "2") (pinfunction "B_2") (pintype "passive"))
      (node (ref "R22") (pin "1") (pinfunction "1_1") (pintype "passive"))
    )
    (net (code "37") (name "Net-(Q8-C)") (class "Default")
      (node (ref "D42") (pin "C") (pinfunction "C_C") (pintype "passive"))
      (node (ref "D45") (pin "A") (pinfunction "A_A") (pintype "passive"))
      (node (ref "Q8") (pin "3") (pinfunction "C_3") (pintype "passive"))
      (node (ref "R24") (pin "2") (pinfunction "2_2") (pintype "passive"))
    )
    (net (code "38") (name "Net-(Q9-B)") (class "Default")
      (node (ref "Q9") (pin "2") (pinfunction "B_2") (pintype "passive"))
      (node (ref "R23") (pin "2") (pinfunction "2_2") (pintype "passive"))
      (node (ref "R25") (pin "1") (pinfunction "1_1") (pintype "passive"))
    )
    (net (code "39") (name "Net-(Q9-C)") (class "Default")
      (node (ref "C6") (pin "1") (pinfunction "1_1") (pintype "passive"))
      (node (ref "D44") (pin "A") (pinfunction "A_A") (pintype "passive"))
      (node (ref "D46") (pin "A") (pinfunction "A_A") (pintype "passive"))
      (node (ref "D49") (pin "C") (pinfunction "C_C") (pintype "passive"))
      (node (ref "Q9") (pin "3") (pinfunction "C_3") (pintype "passive"))
      (node (ref "R27") (pin "2") (pinfunction "2_2") (pintype "passive"))
      (node (ref "R29") (pin "1") (pinfunction "1_1") (pintype "passive"))
      (node (ref "U$2") (pin "AE2") (pinfunction "1_AE2") (pintype "bidirectional"))
    )
    (net (code "40") (name "Net-(Q10-B)") (class "Default")
      (node (ref "D48") (pin "A") (pinfunction "A_A") (pintype "passive"))
      (node (ref "Q10") (pin "2") (pinfunction "B_2") (pintype "passive"))
      (node (ref "R28") (pin "1") (pinfunction "1_1") (pintype "passive"))
    )
    (net (code "41") (name "Net-(Q10-C)") (class "Default")
      (node (ref "C7") (pin "1") (pinfunction "1_1") (pintype "passive"))
      (node (ref "C8") (pin "1") (pinfunction "1_1") (pintype "passive"))
      (node (ref "C8") (pin "2") (pinfunction "2_2") (pintype "passive"))
      (node (ref "D51") (pin "C") (pinfunction "C_C") (pintype "passive"))
      (node (ref "D52") (pin "A") (pinfunction "A_A") (pintype "passive"))
      (node (ref "D53") (pin "C") (pinfunction "C_C") (pintype "passive"))
      (node (ref "Q10") (pin "3") (pinfunction "C_3") (pintype "passive"))
      (node (ref "R30") (pin "2") (pinfunction "2_2") (pintype "passive"))
      (node (ref "R32") (pin "1") (pinfunction "1_1") (pintype "passive"))
      (node (ref "U$2") (pin "AP2") (pinfunction "1_AP2") (pintype "bidirectional"))
    )
    (net (code "42") (name "Net-(Q11-B)") (class "Default")
      (node (ref "C6") (pin "2") (pinfunction "2_2") (pintype "passive"))
      (node (ref "Q11") (pin "2") (pinfunction "B_2") (pintype "passive"))
      (node (ref "R29") (pin "2") (pinfunction "2_2") (pintype "passive"))
    )
    (net (code "43") (name "Net-(Q11-C)") (class "Default")
      (node (ref "D50") (pin "C") (pinfunction "C_C") (pintype "passive"))
      (node (ref "Q11") (pin "3") (pinfunction "C_3") (pintype "passive"))
      (node (ref "R31") (pin "2") (pinfunction "2_2") (pintype "passive"))
      (node (ref "U$2") (pin "AF2") (pinfunction "1_AF2") (pintype "bidirectional"))
    )
    (net (code "44") (name "Net-(Q12-B)") (class "Default")
      (node (ref "Q12") (pin "2") (pinfunction "B_2") (pintype "passive"))
      (node (ref "R32") (pin "2") (pinfunction "2_2") (pintype "passive"))
      (node (ref "R33") (pin "1") (pinfunction "1_1") (pintype "passive"))
    )
    (net (code "45") (name "Net-(Q12-C)") (class "Default")
      (node (ref "C9") (pin "1") (pinfunction "1_1") (pintype "passive"))
      (node (ref "D53") (pin "A") (pinfunction "A_A") (pintype "passive"))
      (node (ref "D54") (pin "A") (pinfunction "A_A") (pintype "passive"))
      (node (ref "D55") (pin "C") (pinfunction "C_C") (pintype "passive"))
      (node (ref "Q12") (pin "3") (pinfunction "C_3") (pintype "passive"))
      (node (ref "R34") (pin "2") (pinfunction "2_2") (pintype "passive"))
      (node (ref "R36") (pin "1") (pinfunction "1_1") (pintype "passive"))
      (node (ref "U$2") (pin "AL2") (pinfunction "1_AL2") (pintype "bidirectional"))
    )
    (net (code "46") (name "Net-(Q13-B)") (class "Default")
      (node (ref "C9") (pin "2") (pinfunction "2_2") (pintype "passive"))
      (node (ref "Q13") (pin "2") (pinfunction "B_2") (pintype "passive"))
      (node (ref "R36") (pin "2") (pinfunction "2_2") (pintype "passive"))
    )
    (net (code "47") (name "Net-(Q13-C)") (class "Default")
      (node (ref "D60") (pin "C") (pinfunction "C_C") (pintype "passive"))
      (node (ref "Q13") (pin "3") (pinfunction "C_3") (pintype "passive"))
      (node (ref "R37") (pin "2") (pinfunction "2_2") (pintype "passive"))
      (node (ref "U$2") (pin "AM2") (pinfunction "1_AM2") (pintype "bidirectional"))
    )
    (net (code "48") (name "Net-(U$2AB-1)") (class "Default")
      (node (ref "D1") (pin "A") (pinfunction "A_A") (pintype "passive"))
      (node (ref "U$2") (pin "AR2") (pinfunction "1_AR2") (pintype "bidirectional"))
    )
    (net (code "49") (name "Net-(U$2AH-1)") (class "Default")
      (node (ref "C1") (pin "2") (pinfunction "2_2") (pintype "passive"))
      (node (ref "U$2") (pin "AU2") (pinfunction "1_AU2") (pintype "bidirectional"))
    )
    (net (code "50") (name "Net-(U$2AT-1)") (class "Default")
      (node (ref "D18") (pin "A") (pinfunction "A_A") (pintype "passive"))
      (node (ref "U$2") (pin "BE2") (pinfunction "1_BE2") (pintype "bidirectional"))
    )
    (net (code "51") (name "Net-(U$2AV-1)") (class "Default")
      (node (ref "D17") (pin "A") (pinfunction "A_A") (pintype "passive"))
      (node (ref "U$2") (pin "BF2") (pinfunction "1_BF2") (pintype "bidirectional"))
    )
    (net (code "52") (name "Net-(U$2AX-1)") (class "Default")
      (node (ref "D16") (pin "A") (pinfunction "A_A") (pintype "passive"))
      (node (ref "U$2") (pin "BH2") (pinfunction "1_BH2") (pintype "bidirectional"))
    )
    (net (code "53") (name "Net-(U$2AZ-1)") (class "Default")
      (node (ref "D15") (pin "A") (pinfunction "A_A") (pintype "passive"))
      (node (ref "U$2") (pin "BJ2") (pinfunction "1_BJ2") (pintype "bidirectional"))
    )
    (net (code "54") (name "Net-(U$2BB-1)") (class "Default")
      (node (ref "D14") (pin "A") (pinfunction "A_A") (pintype "passive"))
      (node (ref "U$2") (pin "BK2") (pinfunction "1_BK2") (pintype "bidirectional"))
    )
    (net (code "55") (name "Net-(U$2BD-1)") (class "Default")
      (node (ref "D13") (pin "A") (pinfunction "A_A") (pintype "passive"))
      (node (ref "U$2") (pin "BL2") (pinfunction "1_BL2") (pintype "bidirectional"))
    )
    (net (code "56") (name "Net-(U$2BF-1)") (class "Default")
      (node (ref "D12") (pin "A") (pinfunction "A_A") (pintype "passive"))
      (node (ref "U$2") (pin "BM2") (pinfunction "1_BM2") (pintype "bidirectional"))
    )
    (net (code "57") (name "Net-(U$2BH-1)") (class "Default")
      (node (ref "D11") (pin "A") (pinfunction "A_A") (pintype "passive"))
      (node (ref "U$2") (pin "BN2") (pinfunction "1_BN2") (pintype "bidirectional"))
    )
    (net (code "58") (name "Net-(U$2BJ-1)") (class "Default")
      (node (ref "D10") (pin "A") (pinfunction "A_A") (pintype "passive"))
      (node (ref "U$2") (pin "BP2") (pinfunction "1_BP2") (pintype "bidirectional"))
    )
    (net (code "59") (name "Net-(U$2BL-1)") (class "Default")
      (node (ref "D9") (pin "A") (pinfunction "A_A") (pintype "passive"))
      (node (ref "U$2") (pin "BR2") (pinfunction "1_BR2") (pintype "bidirectional"))
    )
    (net (code "60") (name "Net-(U$2BN-1)") (class "Default")
      (node (ref "D8") (pin "A") (pinfunction "A_A") (pintype "passive"))
      (node (ref "U$2") (pin "BS2") (pinfunction "1_BS2") (pintype "bidirectional"))
    )
    (net (code "61") (name "Net-(U$2BP-1)") (class "Default")
      (node (ref "D7") (pin "A") (pinfunction "A_A") (pintype "passive"))
      (node (ref "U$2") (pin "BT2") (pinfunction "1_BT2") (pintype "bidirectional"))
    )
    (net (code "62") (name "Net-(U$2BR-1)") (class "Default")
      (node (ref "D6") (pin "A") (pinfunction "A_A") (pintype "passive"))
      (node (ref "U$2") (pin "BU2") (pinfunction "1_BU2") (pintype "bidirectional"))
    )
    (net (code "63") (name "Net-(U$2BT-1)") (class "Default")
      (node (ref "D5") (pin "A") (pinfunction "A_A") (pintype "passive"))
      (node (ref "U$2") (pin "BV2") (pinfunction "1_BV2") (pintype "bidirectional"))
    )
    (net (code "64") (name "Net-(U$2H-1)") (class "Default")
      (node (ref "D29") (pin "A") (pinfunction "A_A") (pintype "passive"))
      (node (ref "U$2") (pin "AD2") (pinfunction "1_AD2") (pintype "bidirectional"))
    )
    (net (code "65") (name "Net-(U$2N-1)") (class "Default")
      (node (ref "C4") (pin "2") (pinfunction "2_2") (pintype "passive"))
      (node (ref "U$2") (pin "AH2") (pinfunction "1_AH2") (pintype "bidirectional"))
    )
    (net (code "66") (name "Net-(U$2R-1)") (class "Default")
      (node (ref "D38") (pin "A") (pinfunction "A_A") (pintype "passive"))
      (node (ref "U$2") (pin "AK2") (pinfunction "1_AK2") (pintype "bidirectional"))
    )
    (net (code "67") (name "Net-(U$2X-1)") (class "Default")
      (node (ref "C7") (pin "2") (pinfunction "2_2") (pintype "passive"))
      (node (ref "U$2") (pin "AN2") (pinfunction "1_AN2") (pintype "bidirectional"))
    )
  )
)
